# IO.net
KiCad netlist of a schematic drawn in Altium Designer
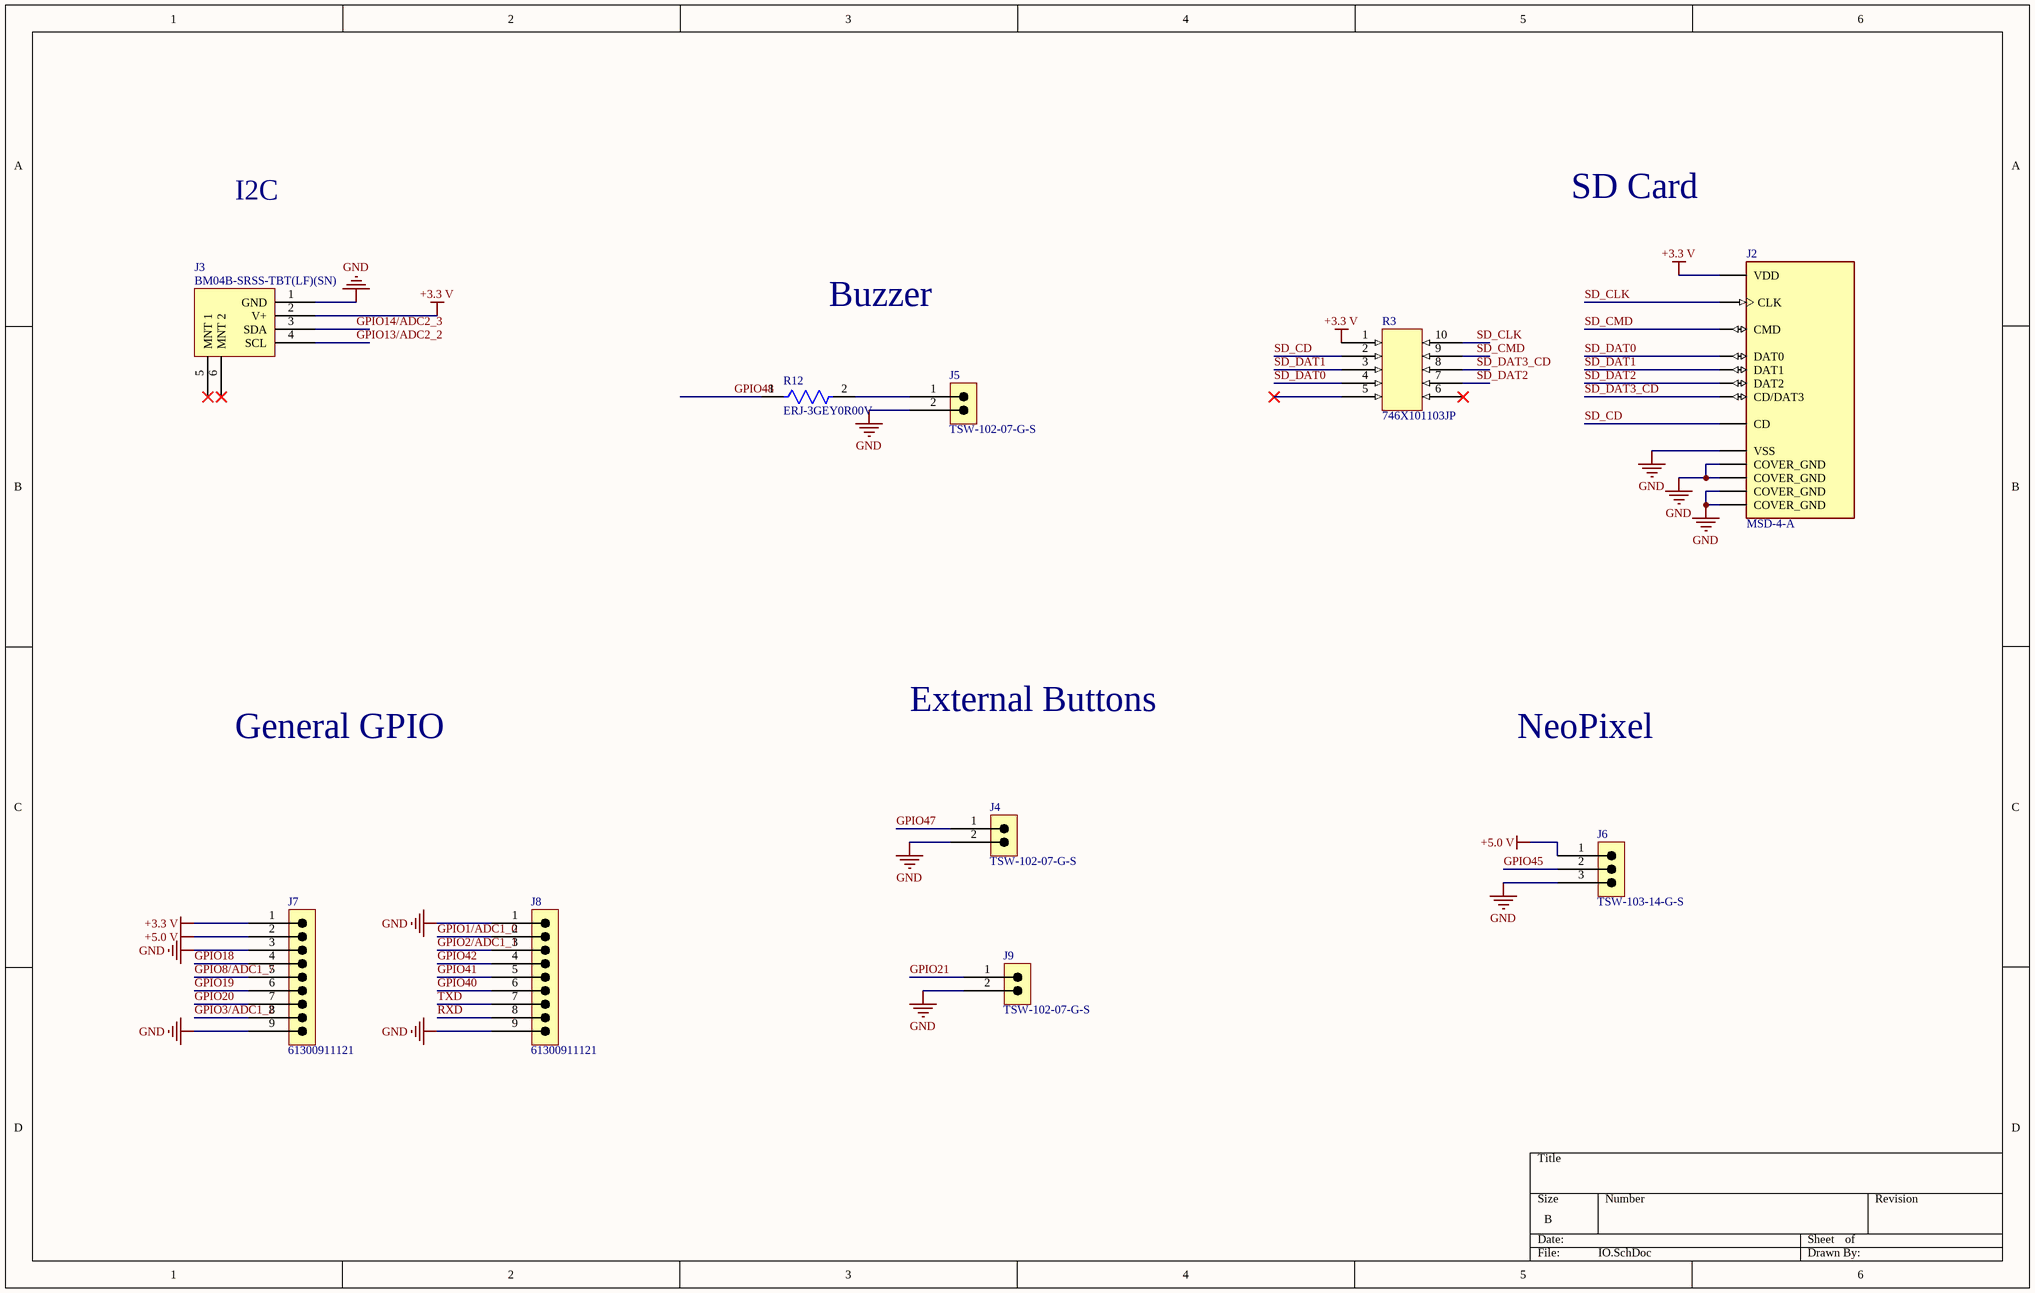
[diagram p0: IO.SchDoc]

(export (version "E")
  (design (tool "Eeschema 10.0.6"))
  (components
    (comp (ref "J2")
      (value "MSD-4-A")
      (footprint "CUI_MSD-4-A")
      (fields (field (name "MF") "CUI Devices"))
      (libsource (lib "C0514760 C0514760") (part "MSD-4-A"))
    )
    (comp (ref "J3")
      (value "BM04B-SRSS-TBT(LF)(SN)")
      (footprint "FP-BM04B-SRSS-TBT_LF_SN-MFG")
      (description "1.0mm Pitch, Ultra-Compact, Low Profile Design, Interchangeable Shrouded Header")
      (libsource (lib "C0514760 C0514760") (part "8e3688c4b118bffc0dd9b7401e414ba"))
    )
    (comp (ref "J4")
      (value "TSW-102-07-G-S")
      (footprint "FP-TSW-102-07-G-S-MFG")
      (libsource (lib "C0514760 C0514760") (part "3bc925449376181038e59eaffc5286c"))
    )
    (comp (ref "J5")
      (value "TSW-102-07-G-S")
      (footprint "FP-TSW-102-07-G-S-MFG")
      (libsource (lib "C0514760 C0514760") (part "3bc925449376181038e59eaffc5286c"))
    )
    (comp (ref "J6")
      (value "TSW-103-14-G-S")
      (footprint "FP-TSW-103-14-G-S-MFG")
      (libsource (lib "C0514760 C0514760") (part "cd3439d6ef35ae5d9b27ec4fdd3e828"))
    )
    (comp (ref "J7")
      (value "61300911121")
      (footprint "61300911121")
      (libsource (lib "C0514760 C0514760") (part "Header_Male_1R_09P"))
    )
    (comp (ref "J8")
      (value "61300911121")
      (footprint "61300911121")
      (libsource (lib "C0514760 C0514760") (part "Header_Male_1R_09P"))
    )
    (comp (ref "J9")
      (value "TSW-102-07-G-S")
      (footprint "FP-TSW-102-07-G-S-MFG")
      (libsource (lib "C0514760 C0514760") (part "3bc925449376181038e59eaffc5286c"))
    )
    (comp (ref "R3")
      (value "746X101103JP")
      (footprint "CAF-127P640X310-10N")
      (fields (field (name "POWER") "248mW") (field (name "TOLERANCE") "5%"))
      (libsource (lib "C0514760 C0514760") (part "746X101103JP-Symbol-1"))
    )
    (comp (ref "R12")
      (value "ERJ-3GEY0R00V")
      (footprint "FP-ERJ-3GEY0R00V-IPC_A")
      (description "Fixed Resistor, Metal Glaze/thick Film, 0.1W, 0ohm, Surface Mount, 0603")
      (fields (field (name "POWER") "100mW"))
      (libsource (lib "C0514760 C0514760") (part "1029c3af85768c4190bb7ad29bc67b5"))
    )
  )
  (nets
    (net (code "1") (name "+3.3 V") (class "Default")
      (node (ref "J2") (pin "4") (pinfunction "VDD_4") (pintype "power_in"))
      (node (ref "J3") (pin "2") (pinfunction "V+_2") (pintype "passive"))
      (node (ref "J7") (pin "1") (pinfunction "1_1") (pintype "passive"))
      (node (ref "R3") (pin "1") (pintype "input"))
    )
    (net (code "2") (name "+5.0 V") (class "Default")
      (node (ref "J6") (pin "1") (pinfunction "1_1") (pintype "passive"))
      (node (ref "J7") (pin "2") (pinfunction "2_2") (pintype "passive"))
    )
    (net (code "3") (name "/GPIO1{slash}ADC1_0") (class "Default")
      (node (ref "J8") (pin "2") (pinfunction "2_2") (pintype "passive"))
    )
    (net (code "4") (name "/GPIO2{slash}ADC1_1") (class "Default")
      (node (ref "J8") (pin "3") (pinfunction "3_3") (pintype "passive"))
    )
    (net (code "5") (name "/GPIO3{slash}ADC1_2") (class "Default")
      (node (ref "J7") (pin "8") (pinfunction "8_8") (pintype "passive"))
    )
    (net (code "6") (name "/GPIO8{slash}ADC1_7") (class "Default")
      (node (ref "J7") (pin "5") (pinfunction "5_5") (pintype "passive"))
    )
    (net (code "7") (name "/GPIO13{slash}ADC2_2") (class "Default")
      (node (ref "J3") (pin "4") (pinfunction "SCL_4") (pintype "passive"))
    )
    (net (code "8") (name "/GPIO14{slash}ADC2_3") (class "Default")
      (node (ref "J3") (pin "3") (pinfunction "SDA_3") (pintype "passive"))
    )
    (net (code "9") (name "/GPIO18") (class "Default")
      (node (ref "J7") (pin "4") (pinfunction "4_4") (pintype "passive"))
    )
    (net (code "10") (name "/GPIO19") (class "Default")
      (node (ref "J7") (pin "6") (pinfunction "6_6") (pintype "passive"))
    )
    (net (code "11") (name "/GPIO20") (class "Default")
      (node (ref "J7") (pin "7") (pinfunction "7_7") (pintype "passive"))
    )
    (net (code "12") (name "/GPIO21") (class "Default")
      (node (ref "J9") (pin "1") (pinfunction "1_1") (pintype "passive"))
    )
    (net (code "13") (name "/GPIO40") (class "Default")
      (node (ref "J8") (pin "6") (pinfunction "6_6") (pintype "passive"))
    )
    (net (code "14") (name "/GPIO41") (class "Default")
      (node (ref "J8") (pin "5") (pinfunction "5_5") (pintype "passive"))
    )
    (net (code "15") (name "/GPIO42") (class "Default")
      (node (ref "J8") (pin "4") (pinfunction "4_4") (pintype "passive"))
    )
    (net (code "16") (name "/GPIO45") (class "Default")
      (node (ref "J6") (pin "2") (pinfunction "2_2") (pintype "passive"))
    )
    (net (code "17") (name "/GPIO47") (class "Default")
      (node (ref "J4") (pin "1") (pinfunction "1_1") (pintype "passive"))
    )
    (net (code "18") (name "/GPIO48") (class "Default")
      (node (ref "R12") (pin "1") (pinfunction "1_1") (pintype "passive"))
    )
    (net (code "19") (name "/RXD") (class "Default")
      (node (ref "J8") (pin "8") (pinfunction "8_8") (pintype "passive"))
    )
    (net (code "20") (name "/SD_CD") (class "Default")
      (node (ref "J2") (pin "CD") (pinfunction "CD_CD") (pintype "passive"))
      (node (ref "R3") (pin "2") (pintype "input"))
    )
    (net (code "21") (name "/SD_CLK") (class "Default")
      (node (ref "J2") (pin "5") (pinfunction "CLK_5") (pintype "input"))
      (node (ref "R3") (pin "10") (pintype "input"))
    )
    (net (code "22") (name "/SD_CMD") (class "Default")
      (node (ref "J2") (pin "3") (pinfunction "CMD_3") (pintype "bidirectional"))
      (node (ref "R3") (pin "9") (pintype "input"))
    )
    (net (code "23") (name "/SD_DAT0") (class "Default")
      (node (ref "J2") (pin "7") (pinfunction "DAT0_7") (pintype "bidirectional"))
      (node (ref "R3") (pin "4") (pintype "input"))
    )
    (net (code "24") (name "/SD_DAT1") (class "Default")
      (node (ref "J2") (pin "8") (pinfunction "DAT1_8") (pintype "bidirectional"))
      (node (ref "R3") (pin "3") (pintype "input"))
    )
    (net (code "25") (name "/SD_DAT2") (class "Default")
      (node (ref "J2") (pin "1") (pinfunction "DAT2_1") (pintype "bidirectional"))
      (node (ref "R3") (pin "7") (pintype "input"))
    )
    (net (code "26") (name "/SD_DAT3_CD") (class "Default")
      (node (ref "J2") (pin "2") (pinfunction "CD/DAT3_2") (pintype "bidirectional"))
      (node (ref "R3") (pin "8") (pintype "input"))
    )
    (net (code "27") (name "/TXD") (class "Default")
      (node (ref "J8") (pin "7") (pinfunction "7_7") (pintype "passive"))
    )
    (net (code "28") (name "GND") (class "Default")
      (node (ref "J2") (pin "6") (pinfunction "VSS_6") (pintype "power_in"))
      (node (ref "J2") (pin "G1") (pinfunction "COVER_GND_G1") (pintype "power_in"))
      (node (ref "J2") (pin "G2") (pinfunction "COVER_GND_G2") (pintype "power_in"))
      (node (ref "J2") (pin "G3") (pinfunction "COVER_GND_G3") (pintype "power_in"))
      (node (ref "J2") (pin "G4") (pinfunction "COVER_GND_G4") (pintype "power_in"))
      (node (ref "J3") (pin "1") (pinfunction "GND_1") (pintype "passive"))
      (node (ref "J4") (pin "2") (pinfunction "2_2") (pintype "passive"))
      (node (ref "J5") (pin "2") (pinfunction "2_2") (pintype "passive"))
      (node (ref "J6") (pin "3") (pinfunction "3_3") (pintype "passive"))
      (node (ref "J7") (pin "3") (pinfunction "3_3") (pintype "passive"))
      (node (ref "J7") (pin "9") (pinfunction "9_9") (pintype "passive"))
      (node (ref "J8") (pin "1") (pinfunction "1_1") (pintype "passive"))
      (node (ref "J8") (pin "9") (pinfunction "9_9") (pintype "passive"))
      (node (ref "J9") (pin "2") (pinfunction "2_2") (pintype "passive"))
    )
    (net (code "29") (name "Net-(J5-Pad1)") (class "Default")
      (node (ref "J5") (pin "1") (pinfunction "1_1") (pintype "passive"))
      (node (ref "R12") (pin "2") (pinfunction "2_2") (pintype "passive"))
    )
    (net (code "30") (name "unconnected-(J3-MNT_1-Pad5)") (class "Default")
      (node (ref "J3") (pin "5") (pinfunction "MNT_1_5") (pintype "passive+no_connect"))
    )
    (net (code "31") (name "unconnected-(J3-MNT_2-Pad6)") (class "Default")
      (node (ref "J3") (pin "6") (pinfunction "MNT_2_6") (pintype "passive+no_connect"))
    )
    (net (code "32") (name "unconnected-(R3-Pad5)") (class "Default")
      (node (ref "R3") (pin "5") (pintype "input+no_connect"))
    )
    (net (code "33") (name "unconnected-(R3-Pad6)") (class "Default")
      (node (ref "R3") (pin "6") (pintype "input+no_connect"))
    )
  )
)
